# HYDRA_V3_CAMERA.net
KiCad netlist of a schematic drawn in Altium Designer
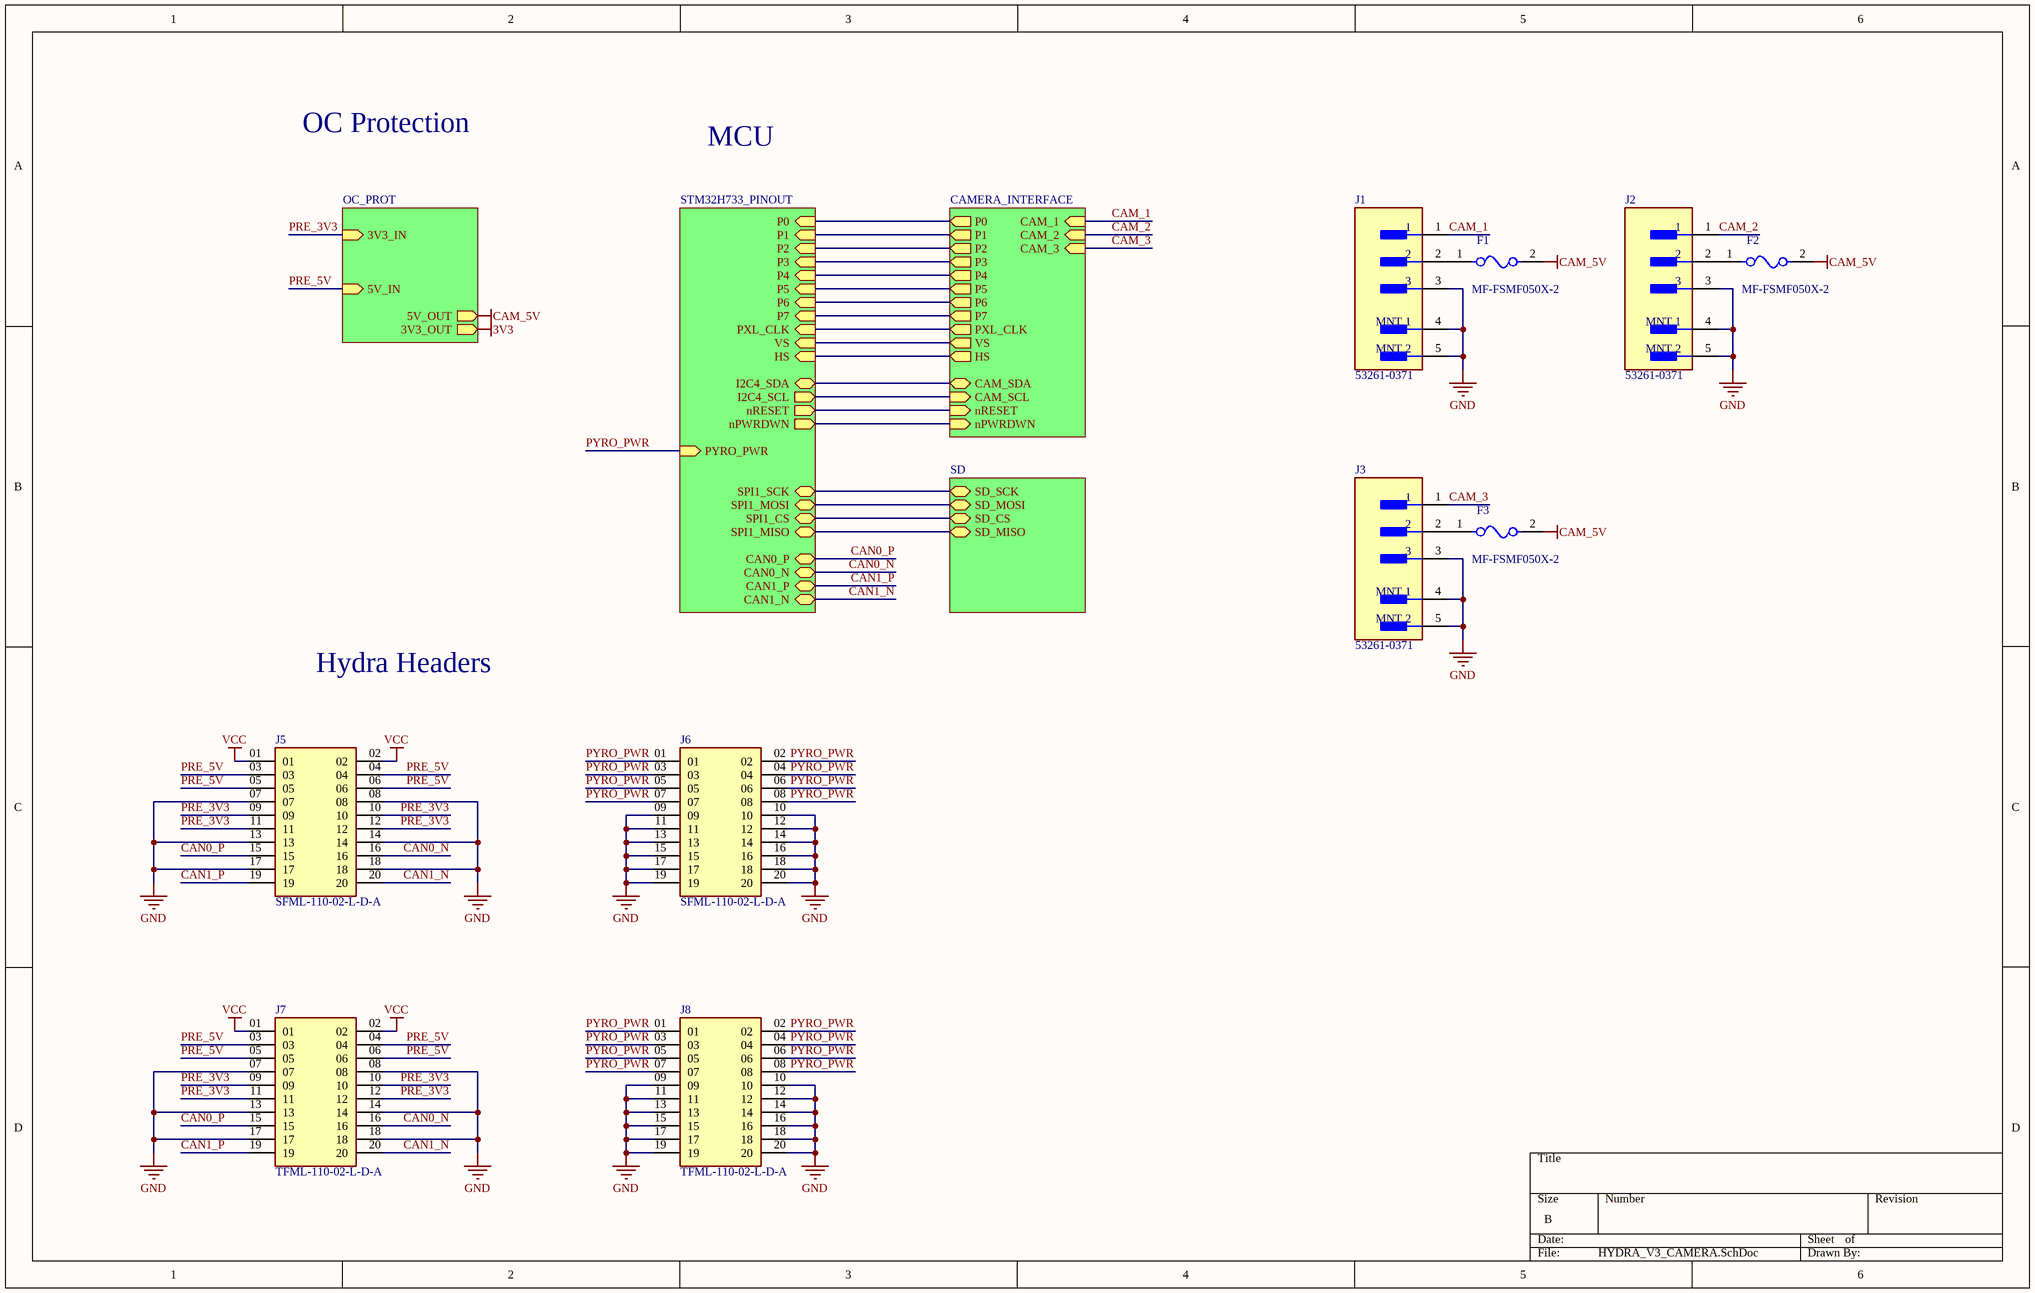
[diagram p0: HYDRA_V3_CAMERA.SchDoc]

(export (version "E")
  (design (tool "Eeschema 10.0.6"))
  (components
    (comp (ref "F1")
      (value "MF-FSMF050X-2")
      (footprint "FP-MF-FSMF-MFG")
      (description "PTC RESET FUSE 6V 500MA 0603")
      (fields
        (field (name "MANUFACTURER") "Bourns Inc.")
        (field (name "OCTOPART") "https://octopart.com/mf-fsmf050x-2-bourns-10470804")
      )
      (libsource (lib "Altium Content Vault") (part "5bcf9b9f640e542cf0359d10258e979"))
    )
    (comp (ref "F2")
      (value "MF-FSMF050X-2")
      (footprint "FP-MF-FSMF-MFG")
      (description "PTC RESET FUSE 6V 500MA 0603")
      (fields
        (field (name "MANUFACTURER") "Bourns Inc.")
        (field (name "OCTOPART") "https://octopart.com/mf-fsmf050x-2-bourns-10470804")
      )
      (libsource (lib "Altium Content Vault") (part "5bcf9b9f640e542cf0359d10258e979"))
    )
    (comp (ref "F3")
      (value "MF-FSMF050X-2")
      (footprint "FP-MF-FSMF-MFG")
      (description "PTC RESET FUSE 6V 500MA 0603")
      (fields
        (field (name "MANUFACTURER") "Bourns Inc.")
        (field (name "OCTOPART") "https://octopart.com/mf-fsmf050x-2-bourns-10470804")
      )
      (libsource (lib "Altium Content Vault") (part "5bcf9b9f640e542cf0359d10258e979"))
    )
    (comp (ref "J1")
      (value "53261-0371")
      (footprint "FP-53261-0371-MFG")
      (description "CONN HEADER SMD R/A 3POS 1.25MM")
      (fields
        (field (name "MANUFACTURER") "Molex")
        (field (name "OCTOPART") "https://octopart.com/53261-0371-molex-655314")
      )
      (libsource (lib "Altium Content Vault") (part "13850a6865a90496d8e6d51657cef87"))
    )
    (comp (ref "J2")
      (value "53261-0371")
      (footprint "FP-53261-0371-MFG")
      (description "CONN HEADER SMD R/A 3POS 1.25MM")
      (fields
        (field (name "MANUFACTURER") "Molex")
        (field (name "OCTOPART") "https://octopart.com/53261-0371-molex-655314")
      )
      (libsource (lib "Altium Content Vault") (part "13850a6865a90496d8e6d51657cef87"))
    )
    (comp (ref "J3")
      (value "53261-0371")
      (footprint "FP-53261-0371-MFG")
      (description "CONN HEADER SMD R/A 3POS 1.25MM")
      (fields
        (field (name "MANUFACTURER") "Molex")
        (field (name "OCTOPART") "https://octopart.com/53261-0371-molex-655314")
      )
      (libsource (lib "Altium Content Vault") (part "13850a6865a90496d8e6d51657cef87"))
    )
    (comp (ref "J5")
      (value "SFML-110-02-L-D-A")
      (footprint "SFML-110-02-L-D-A-Footprint-1")
      (description "Headers & Wire Housings .050 Tiger Eye High-Reliability Locking Socket Strip")
      (libsource (lib "uORocketry Hardware") (part "SFML-110-02-L-D-A"))
    )
    (comp (ref "J6")
      (value "SFML-110-02-L-D-A")
      (footprint "SFML-110-02-L-D-A-Footprint-1")
      (description "Headers & Wire Housings .050 Tiger Eye High-Reliability Locking Socket Strip")
      (libsource (lib "uORocketry Hardware") (part "SFML-110-02-L-D-A"))
    )
    (comp (ref "J7")
      (value "TFML-110-02-L-D-A")
      (footprint "TFML-110-02-L-D-A-Footprint-1")
      (description "Conn Shrouded Header (4 Sides) HDR 20 POS 1.27mm Solder ST Top Entry SMD TIGER EYE™ Tube")
      (libsource (lib "uORocketry Hardware") (part "TFML-110-02-L-D-A"))
    )
    (comp (ref "J8")
      (value "TFML-110-02-L-D-A")
      (footprint "TFML-110-02-L-D-A-Footprint-1")
      (description "Conn Shrouded Header (4 Sides) HDR 20 POS 1.27mm Solder ST Top Entry SMD TIGER EYE™ Tube")
      (libsource (lib "uORocketry Hardware") (part "TFML-110-02-L-D-A"))
    )
  )
  (nets
    (net (code "1") (name "/CAM_1") (class "Default")
      (node (ref "J1") (pin "1") (pinfunction "1_1") (pintype "passive"))
    )
    (net (code "2") (name "/CAM_2") (class "Default")
      (node (ref "J2") (pin "1") (pinfunction "1_1") (pintype "passive"))
    )
    (net (code "3") (name "/CAM_3") (class "Default")
      (node (ref "J3") (pin "1") (pinfunction "1_1") (pintype "passive"))
    )
    (net (code "5") (name "/CAN0_N") (class "Default")
      (node (ref "J5") (pin "16") (pinfunction "16_16") (pintype "passive"))
      (node (ref "J7") (pin "16") (pinfunction "16_16") (pintype "passive"))
    )
    (net (code "6") (name "/CAN0_P") (class "Default")
      (node (ref "J5") (pin "15") (pinfunction "15_15") (pintype "passive"))
      (node (ref "J7") (pin "15") (pinfunction "15_15") (pintype "passive"))
    )
    (net (code "7") (name "/CAN1_N") (class "Default")
      (node (ref "J5") (pin "20") (pinfunction "20_20") (pintype "passive"))
      (node (ref "J7") (pin "20") (pinfunction "20_20") (pintype "passive"))
    )
    (net (code "8") (name "/CAN1_P") (class "Default")
      (node (ref "J5") (pin "19") (pinfunction "19_19") (pintype "passive"))
      (node (ref "J7") (pin "19") (pinfunction "19_19") (pintype "passive"))
    )
    (net (code "19") (name "/PRE_3V3") (class "Default")
      (node (ref "J5") (pin "09") (pinfunction "09_09") (pintype "passive"))
      (node (ref "J5") (pin "10") (pinfunction "10_10") (pintype "passive"))
      (node (ref "J5") (pin "11") (pinfunction "11_11") (pintype "passive"))
      (node (ref "J5") (pin "12") (pinfunction "12_12") (pintype "passive"))
      (node (ref "J7") (pin "09") (pinfunction "09_09") (pintype "passive"))
      (node (ref "J7") (pin "10") (pinfunction "10_10") (pintype "passive"))
      (node (ref "J7") (pin "11") (pinfunction "11_11") (pintype "passive"))
      (node (ref "J7") (pin "12") (pinfunction "12_12") (pintype "passive"))
    )
    (net (code "20") (name "/PRE_5V") (class "Default")
      (node (ref "J5") (pin "03") (pinfunction "03_03") (pintype "passive"))
      (node (ref "J5") (pin "04") (pinfunction "04_04") (pintype "passive"))
      (node (ref "J5") (pin "05") (pinfunction "05_05") (pintype "passive"))
      (node (ref "J5") (pin "06") (pinfunction "06_06") (pintype "passive"))
      (node (ref "J7") (pin "03") (pinfunction "03_03") (pintype "passive"))
      (node (ref "J7") (pin "04") (pinfunction "04_04") (pintype "passive"))
      (node (ref "J7") (pin "05") (pinfunction "05_05") (pintype "passive"))
      (node (ref "J7") (pin "06") (pinfunction "06_06") (pintype "passive"))
    )
    (net (code "22") (name "/PYRO_PWR") (class "Default")
      (node (ref "J6") (pin "01") (pinfunction "01_01") (pintype "passive"))
      (node (ref "J6") (pin "02") (pinfunction "02_02") (pintype "passive"))
      (node (ref "J6") (pin "03") (pinfunction "03_03") (pintype "passive"))
      (node (ref "J6") (pin "04") (pinfunction "04_04") (pintype "passive"))
      (node (ref "J6") (pin "05") (pinfunction "05_05") (pintype "passive"))
      (node (ref "J6") (pin "06") (pinfunction "06_06") (pintype "passive"))
      (node (ref "J6") (pin "07") (pinfunction "07_07") (pintype "passive"))
      (node (ref "J6") (pin "08") (pinfunction "08_08") (pintype "passive"))
      (node (ref "J8") (pin "01") (pinfunction "01_01") (pintype "passive"))
      (node (ref "J8") (pin "02") (pinfunction "02_02") (pintype "passive"))
      (node (ref "J8") (pin "03") (pinfunction "03_03") (pintype "passive"))
      (node (ref "J8") (pin "04") (pinfunction "04_04") (pintype "passive"))
      (node (ref "J8") (pin "05") (pinfunction "05_05") (pintype "passive"))
      (node (ref "J8") (pin "06") (pinfunction "06_06") (pintype "passive"))
      (node (ref "J8") (pin "07") (pinfunction "07_07") (pintype "passive"))
      (node (ref "J8") (pin "08") (pinfunction "08_08") (pintype "passive"))
    )
    (net (code "31") (name "CAM_5V") (class "Default")
      (node (ref "F1") (pin "2") (pinfunction "2_2") (pintype "passive"))
      (node (ref "F2") (pin "2") (pinfunction "2_2") (pintype "passive"))
      (node (ref "F3") (pin "2") (pinfunction "2_2") (pintype "passive"))
    )
    (net (code "32") (name "GND") (class "Default")
      (node (ref "J1") (pin "3") (pinfunction "3_3") (pintype "passive"))
      (node (ref "J1") (pin "4") (pinfunction "MNT_1_4") (pintype "passive"))
      (node (ref "J1") (pin "5") (pinfunction "MNT_2_5") (pintype "passive"))
      (node (ref "J2") (pin "3") (pinfunction "3_3") (pintype "passive"))
      (node (ref "J2") (pin "4") (pinfunction "MNT_1_4") (pintype "passive"))
      (node (ref "J2") (pin "5") (pinfunction "MNT_2_5") (pintype "passive"))
      (node (ref "J3") (pin "3") (pinfunction "3_3") (pintype "passive"))
      (node (ref "J3") (pin "4") (pinfunction "MNT_1_4") (pintype "passive"))
      (node (ref "J3") (pin "5") (pinfunction "MNT_2_5") (pintype "passive"))
      (node (ref "J5") (pin "07") (pinfunction "07_07") (pintype "passive"))
      (node (ref "J5") (pin "08") (pinfunction "08_08") (pintype "passive"))
      (node (ref "J5") (pin "13") (pinfunction "13_13") (pintype "passive"))
      (node (ref "J5") (pin "14") (pinfunction "14_14") (pintype "passive"))
      (node (ref "J5") (pin "17") (pinfunction "17_17") (pintype "passive"))
      (node (ref "J5") (pin "18") (pinfunction "18_18") (pintype "passive"))
      (node (ref "J6") (pin "09") (pinfunction "09_09") (pintype "passive"))
      (node (ref "J6") (pin "10") (pinfunction "10_10") (pintype "passive"))
      (node (ref "J6") (pin "11") (pinfunction "11_11") (pintype "passive"))
      (node (ref "J6") (pin "12") (pinfunction "12_12") (pintype "passive"))
      (node (ref "J6") (pin "13") (pinfunction "13_13") (pintype "passive"))
      (node (ref "J6") (pin "14") (pinfunction "14_14") (pintype "passive"))
      (node (ref "J6") (pin "15") (pinfunction "15_15") (pintype "passive"))
      (node (ref "J6") (pin "16") (pinfunction "16_16") (pintype "passive"))
      (node (ref "J6") (pin "17") (pinfunction "17_17") (pintype "passive"))
      (node (ref "J6") (pin "18") (pinfunction "18_18") (pintype "passive"))
      (node (ref "J6") (pin "19") (pinfunction "19_19") (pintype "passive"))
      (node (ref "J6") (pin "20") (pinfunction "20_20") (pintype "passive"))
      (node (ref "J7") (pin "07") (pinfunction "07_07") (pintype "passive"))
      (node (ref "J7") (pin "08") (pinfunction "08_08") (pintype "passive"))
      (node (ref "J7") (pin "13") (pinfunction "13_13") (pintype "passive"))
      (node (ref "J7") (pin "14") (pinfunction "14_14") (pintype "passive"))
      (node (ref "J7") (pin "17") (pinfunction "17_17") (pintype "passive"))
      (node (ref "J7") (pin "18") (pinfunction "18_18") (pintype "passive"))
      (node (ref "J8") (pin "09") (pinfunction "09_09") (pintype "passive"))
      (node (ref "J8") (pin "10") (pinfunction "10_10") (pintype "passive"))
      (node (ref "J8") (pin "11") (pinfunction "11_11") (pintype "passive"))
      (node (ref "J8") (pin "12") (pinfunction "12_12") (pintype "passive"))
      (node (ref "J8") (pin "13") (pinfunction "13_13") (pintype "passive"))
      (node (ref "J8") (pin "14") (pinfunction "14_14") (pintype "passive"))
      (node (ref "J8") (pin "15") (pinfunction "15_15") (pintype "passive"))
      (node (ref "J8") (pin "16") (pinfunction "16_16") (pintype "passive"))
      (node (ref "J8") (pin "17") (pinfunction "17_17") (pintype "passive"))
      (node (ref "J8") (pin "18") (pinfunction "18_18") (pintype "passive"))
      (node (ref "J8") (pin "19") (pinfunction "19_19") (pintype "passive"))
      (node (ref "J8") (pin "20") (pinfunction "20_20") (pintype "passive"))
    )
    (net (code "33") (name "Net-(F1-Pad1)") (class "Default")
      (node (ref "F1") (pin "1") (pinfunction "1_1") (pintype "passive"))
      (node (ref "J1") (pin "2") (pinfunction "2_2") (pintype "passive"))
    )
    (net (code "34") (name "Net-(F2-Pad1)") (class "Default")
      (node (ref "F2") (pin "1") (pinfunction "1_1") (pintype "passive"))
      (node (ref "J2") (pin "2") (pinfunction "2_2") (pintype "passive"))
    )
    (net (code "35") (name "Net-(F3-Pad1)") (class "Default")
      (node (ref "F3") (pin "1") (pinfunction "1_1") (pintype "passive"))
      (node (ref "J3") (pin "2") (pinfunction "2_2") (pintype "passive"))
    )
    (net (code "36") (name "VCC") (class "Default")
      (node (ref "J5") (pin "01") (pinfunction "01_01") (pintype "passive"))
      (node (ref "J5") (pin "02") (pinfunction "02_02") (pintype "passive"))
      (node (ref "J7") (pin "01") (pinfunction "01_01") (pintype "passive"))
      (node (ref "J7") (pin "02") (pinfunction "02_02") (pintype "passive"))
    )
  )
)
